# capsenbrd.net
KiCad netlist of a schematic drawn in EAGLE
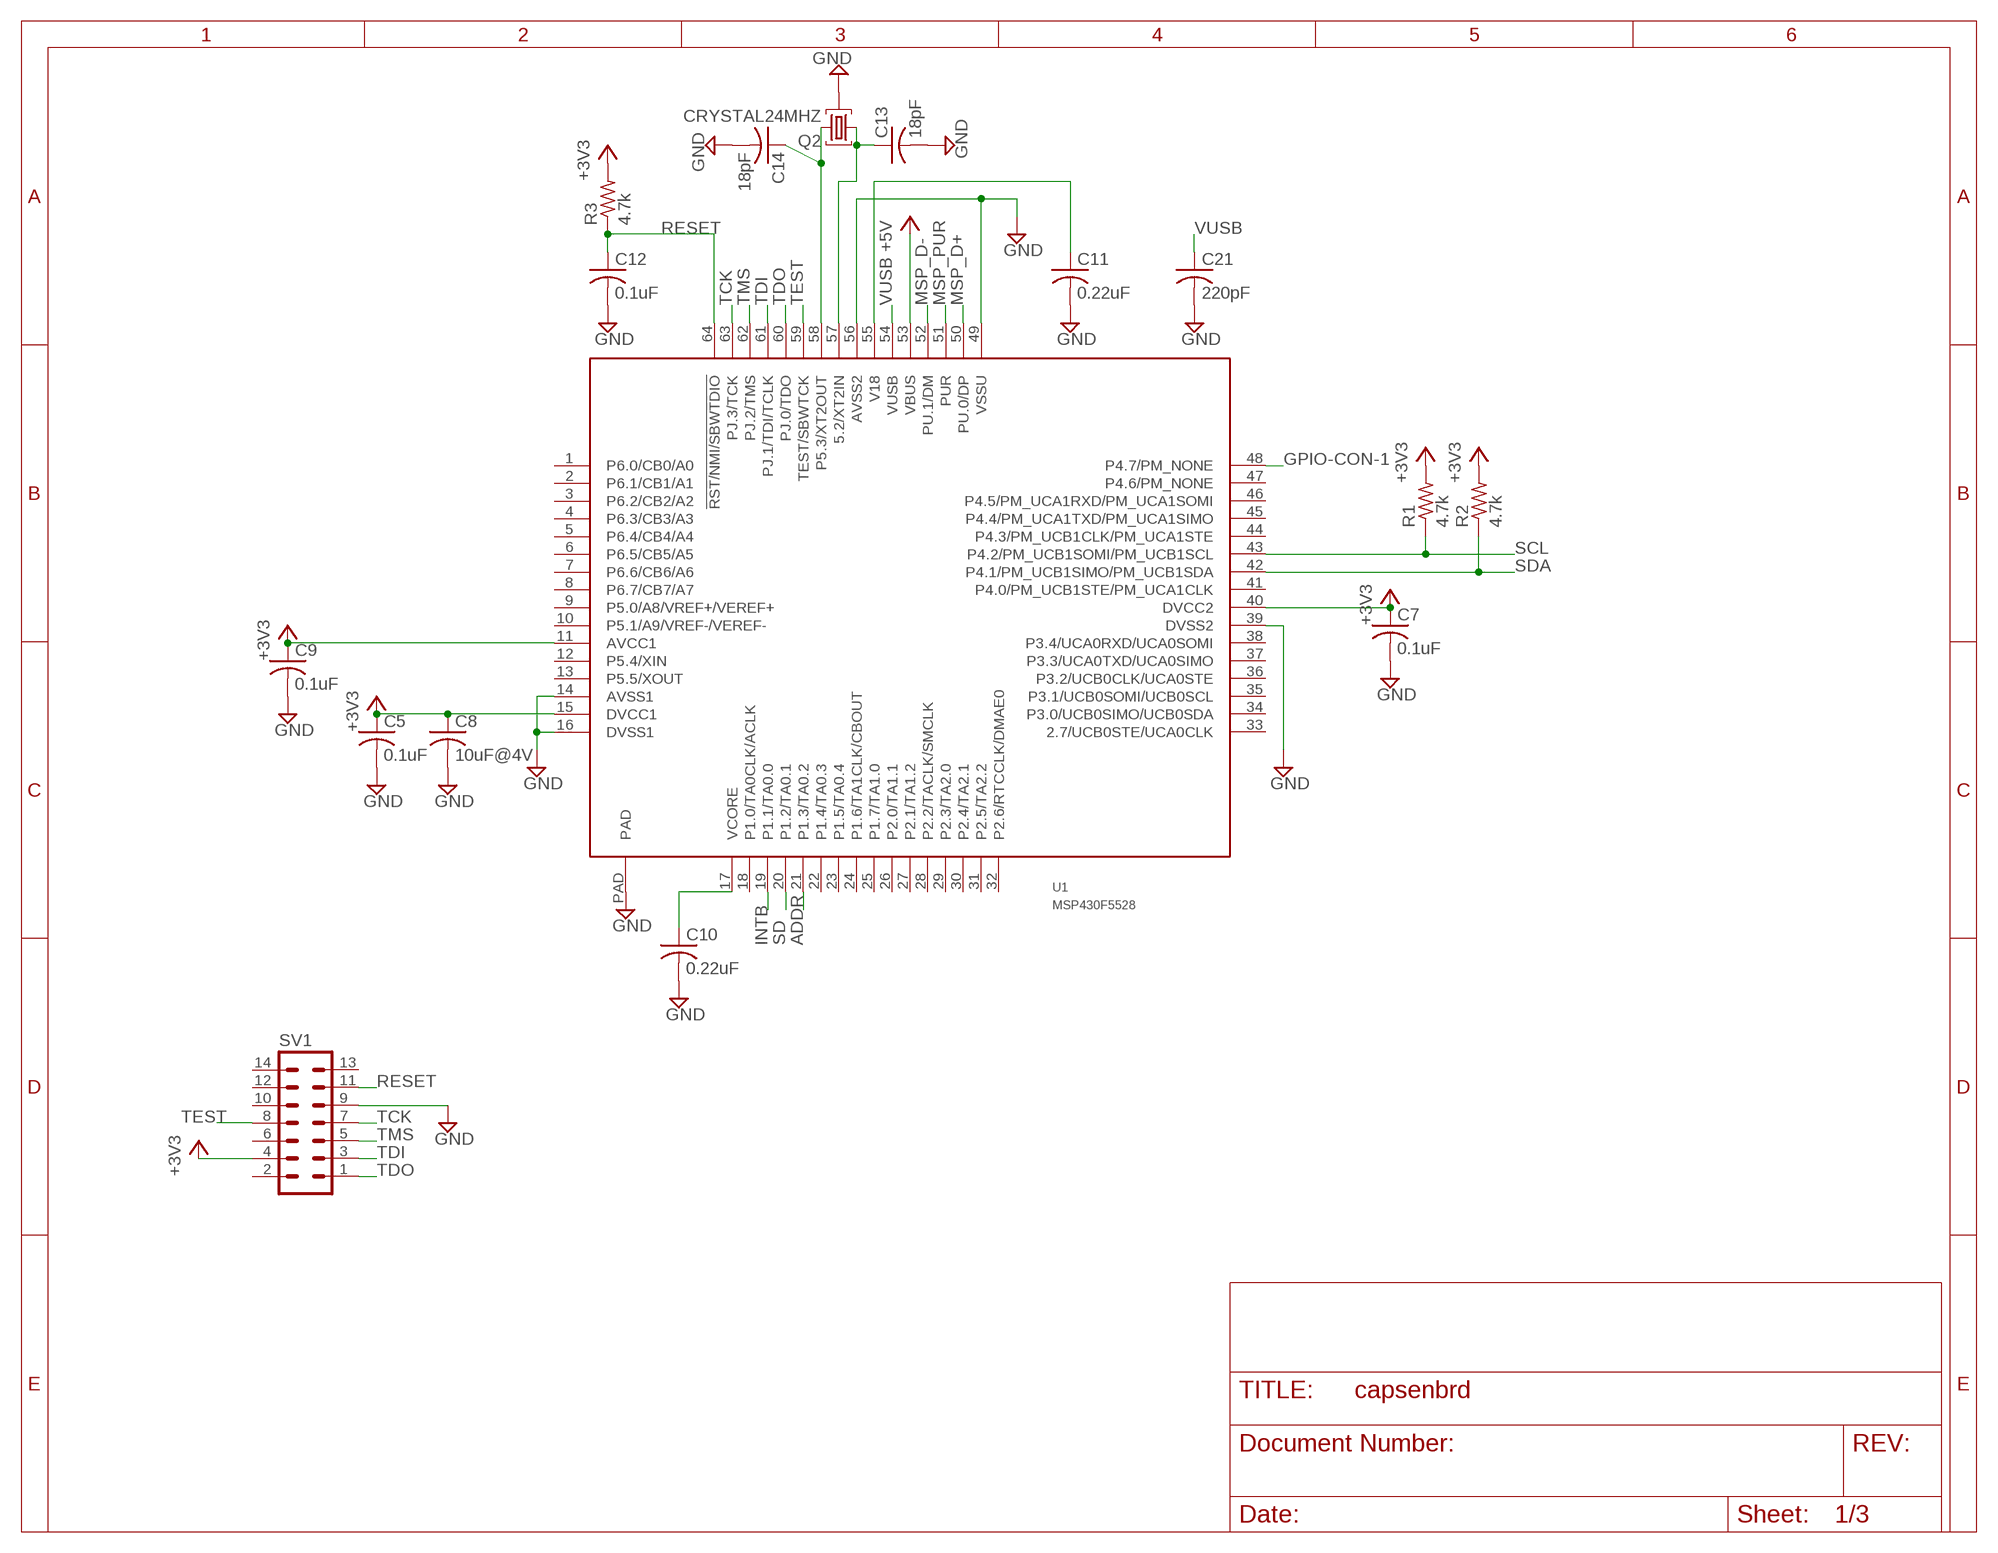
[diagram p0: schematic, sheet 1]
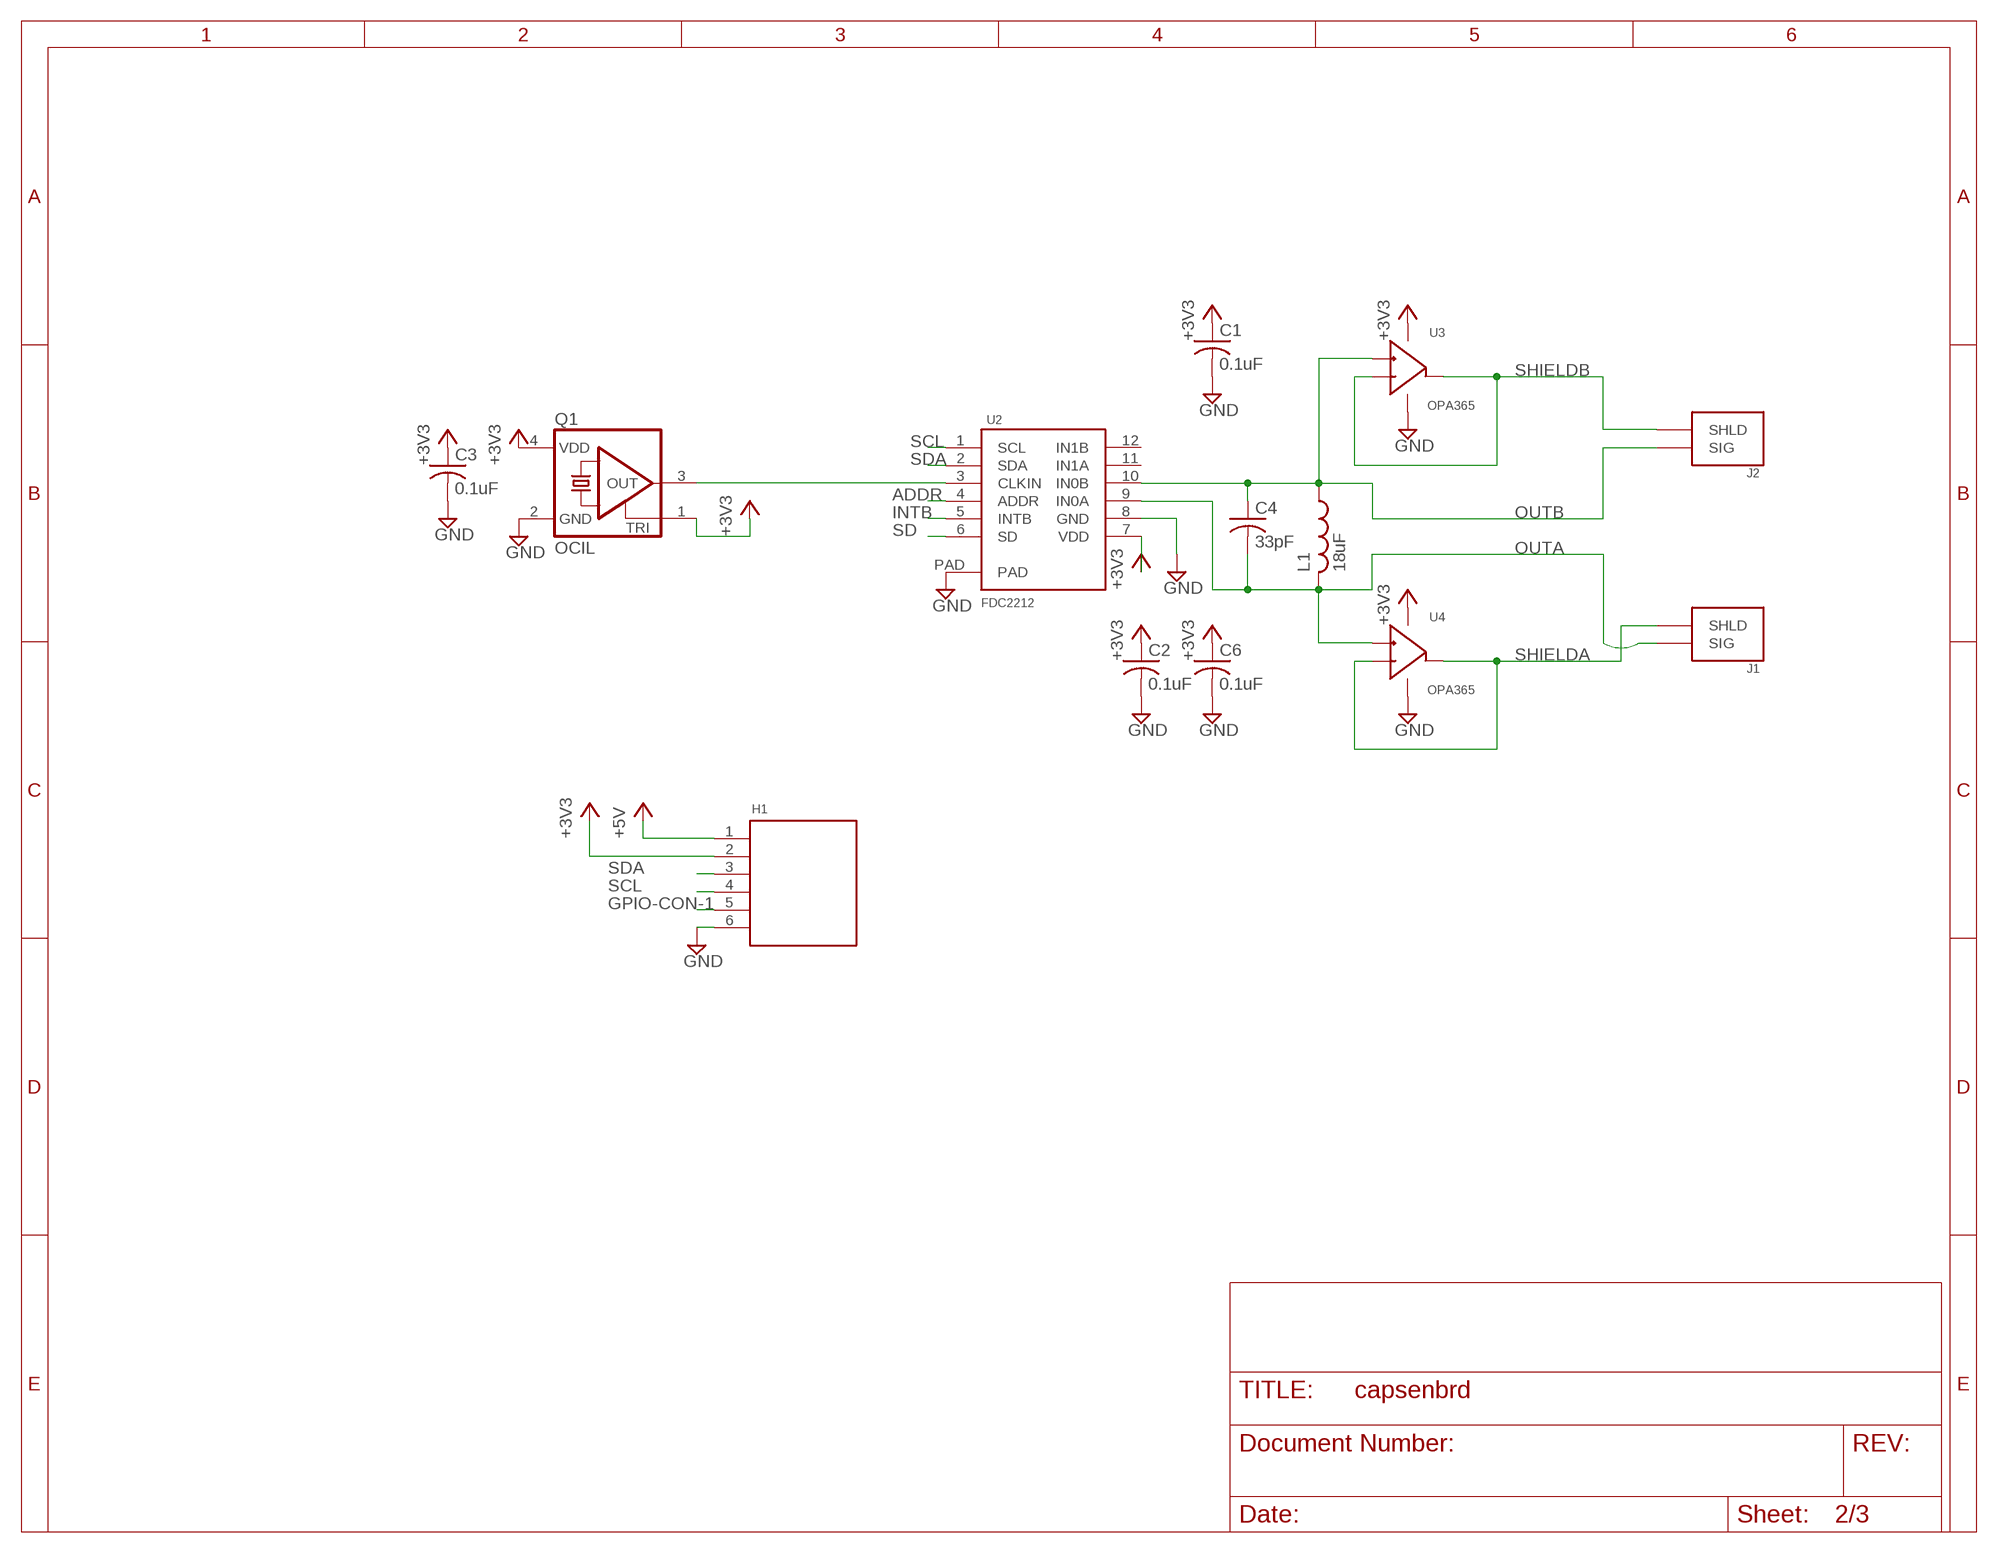
[diagram p1: schematic, sheet 2]
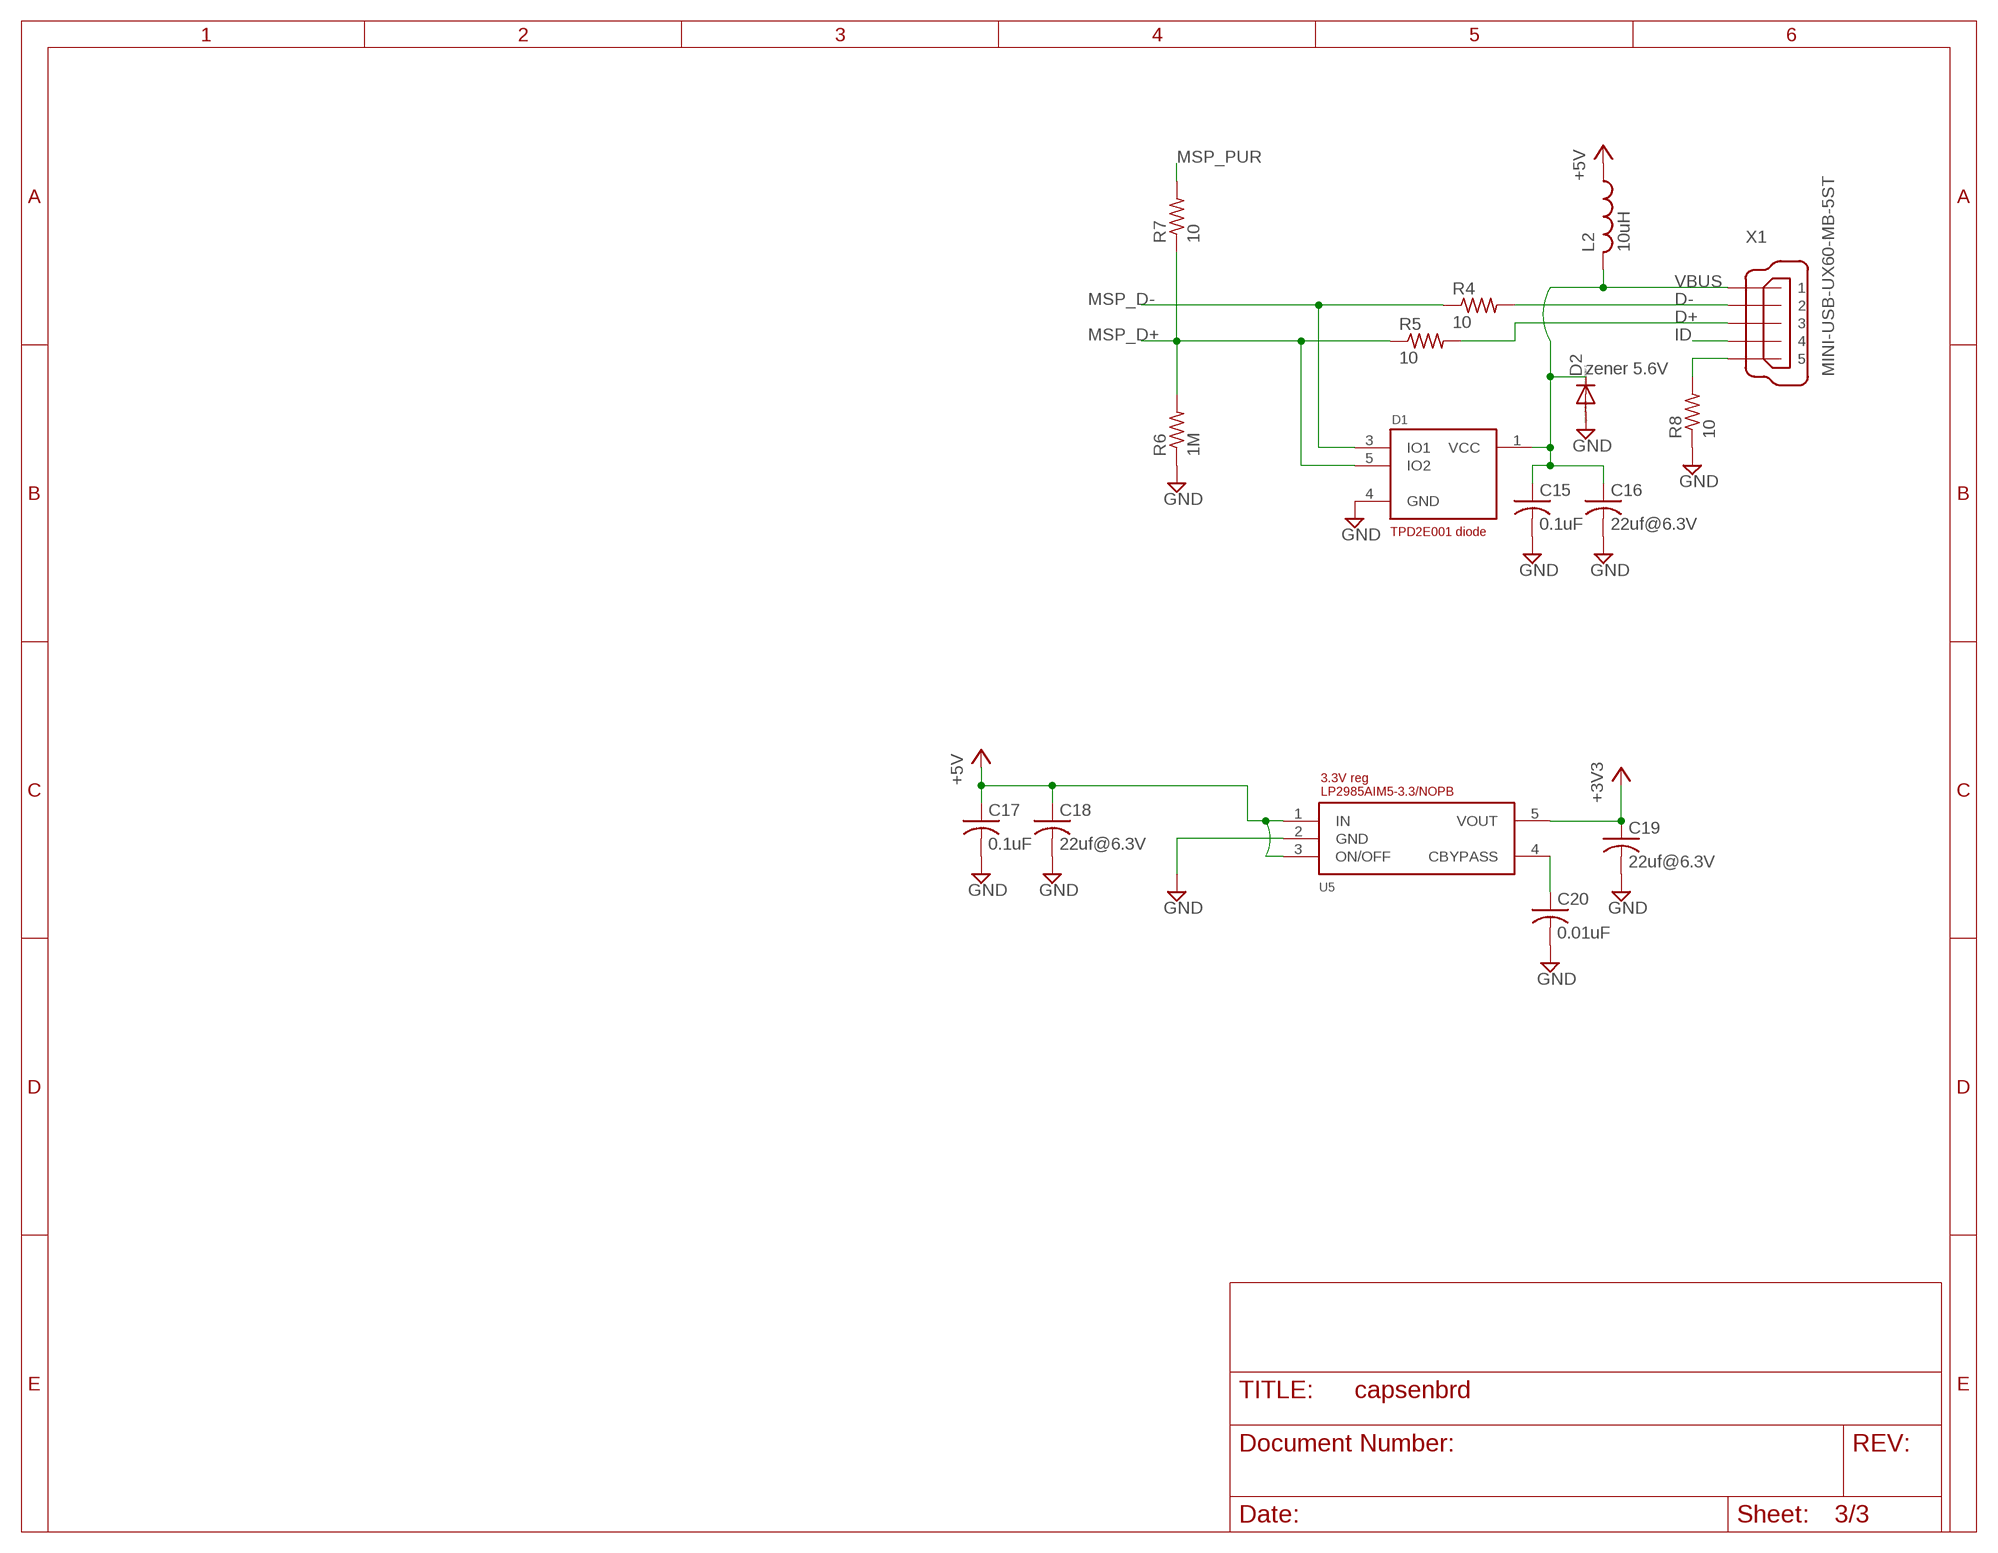
[diagram p2: schematic, sheet 3]

(export (version "E")
  (design (tool "Eeschema 10.0.6"))
  (components
    (comp (ref "C1")
      (value "0.1uF")
      (footprint "eagle-import:C0603")
      (fields (field (name "MFG") "yageo") (field (name "MPN") "CC0603KRX7R7BB104"))
      (libsource (lib "eagle-import") (part "C-USC06030.1UF"))
    )
    (comp (ref "C2")
      (value "0.1uF")
      (footprint "eagle-import:C0603")
      (fields (field (name "MFG") "yageo") (field (name "MPN") "CC0603KRX7R7BB104"))
      (libsource (lib "eagle-import") (part "C-USC06030.1UF"))
    )
    (comp (ref "C3")
      (value "0.1uF")
      (footprint "eagle-import:C0603")
      (fields (field (name "MFG") "yageo") (field (name "MPN") "CC0603KRX7R7BB104"))
      (libsource (lib "eagle-import") (part "C-USC06030.1UF"))
    )
    (comp (ref "C4")
      (value "33pF")
      (footprint "eagle-import:C0603")
      (fields (field (name "MFG") "murata") (field (name "MPN") "GRM1885C1H330JA01D"))
      (libsource (lib "eagle-import") (part "C-USC0603-33PF-"))
    )
    (comp (ref "C6")
      (value "0.1uF")
      (footprint "eagle-import:C0603")
      (fields (field (name "MFG") "yageo") (field (name "MPN") "CC0603KRX7R7BB104"))
      (libsource (lib "eagle-import") (part "C-USC06030.1UF"))
    )
    (comp (ref "H1")
      (value "CON-6-1")
      (footprint "eagle-import:10114828-10106LF")
      (fields (field (name "MFG") "FCI") (field (name "MPN") " 10114828-10106LF "))
      (libsource (lib "eagle-import") (part "CON-6-1"))
    )
    (comp (ref "J1")
      (value "SMA-SMT-")
      (footprint "eagle-import:0732511352")
      (fields (field (name "MFG") "molex") (field (name "MPN") "0732511352"))
      (libsource (lib "eagle-import") (part "SMA-SMT-"))
    )
    (comp (ref "J2")
      (value "SMA-SMT-")
      (footprint "eagle-import:0732511352")
      (fields (field (name "MFG") "molex") (field (name "MPN") "0732511352"))
      (libsource (lib "eagle-import") (part "SMA-SMT-"))
    )
    (comp (ref "L1")
      (value "18uF")
      (footprint "eagle-import:L1210")
      (fields (field (name "MFG") "bourns") (field (name "MPN") " CMH322522-180KL "))
      (libsource (lib "eagle-import") (part "L-USL1210-18UF-"))
    )
    (comp (ref "Q1")
      (value "OCIL")
      (footprint "eagle-import:625L3C040M00000")
      (fields (field (name "MFG") "CTS") (field (name "MPN") "625L3C040M00000"))
      (libsource (lib "eagle-import") (part "OCIL"))
    )
    (comp (ref "U2")
      (value "FDC2212")
      (footprint "eagle-import:-WSON")
      (fields (field (name "MFG") "TI"))
      (libsource (lib "eagle-import") (part "FDC2212"))
    )
    (comp (ref "U3")
      (value "OPA365")
      (footprint "eagle-import:-DBV")
      (fields (field (name "MFG") "TI") (field (name "MPN") "OPA365AIDBVR"))
      (libsource (lib "eagle-import") (part "OPA365"))
    )
    (comp (ref "U4")
      (value "OPA365")
      (footprint "eagle-import:-DBV")
      (fields (field (name "MFG") "TI") (field (name "MPN") "OPA365AIDBVR"))
      (libsource (lib "eagle-import") (part "OPA365"))
    )
    (comp (ref "C15")
      (value "0.1uF")
      (footprint "eagle-import:C0603")
      (fields (field (name "MFG") "yageo") (field (name "MPN") "CC0603KRX7R7BB104"))
      (libsource (lib "eagle-import") (part "C-USC06030.1UF"))
    )
    (comp (ref "C16")
      (value "22uf@6.3V")
      (footprint "eagle-import:C0603")
      (fields (field (name "MFG") "samsung") (field (name "MPN") "CL10A226MQ8NRNC"))
      (libsource (lib "eagle-import") (part "C-USC060322UF"))
    )
    (comp (ref "C17")
      (value "0.1uF")
      (footprint "eagle-import:C0603")
      (fields (field (name "MFG") "yageo") (field (name "MPN") "CC0603KRX7R7BB104"))
      (libsource (lib "eagle-import") (part "C-USC06030.1UF"))
    )
    (comp (ref "C18")
      (value "22uf@6.3V")
      (footprint "eagle-import:C0603")
      (fields (field (name "MFG") "samsung") (field (name "MPN") "CL10A226MQ8NRNC"))
      (libsource (lib "eagle-import") (part "C-USC060322UF"))
    )
    (comp (ref "C19")
      (value "22uf@6.3V")
      (footprint "eagle-import:C0603")
      (fields (field (name "MFG") "samsung") (field (name "MPN") "CL10A226MQ8NRNC"))
      (libsource (lib "eagle-import") (part "C-USC060322UF"))
    )
    (comp (ref "C20")
      (value "0.01uF")
      (footprint "eagle-import:C0603")
      (fields (field (name "MFG") "murata") (field (name "MPN") "GRM1885C1H103JA01D"))
      (libsource (lib "eagle-import") (part "C-USC0603-0.01UF-"))
    )
    (comp (ref "D1")
      (value "USB-DIODE")
      (footprint "eagle-import:-DRL")
      (fields (field (name "MFG") "ti") (field (name "MPN") "TPD2E001DRLRG4"))
      (libsource (lib "eagle-import") (part "USB-DIODE"))
    )
    (comp (ref "D2")
      (value "zener 5.6V")
      (footprint "eagle-import:SOD123")
      (fields (field (name "MFG") "diodes inc") (field (name "MPN") " MMSZ5232B-7-F"))
      (libsource (lib "eagle-import") (part "DIODE-SOD123"))
    )
    (comp (ref "L2")
      (value "10uH")
      (footprint "eagle-import:VLS201610ET")
      (fields (field (name "MFG") "tdk") (field (name "MPN") " VLS201610ET-100M "))
      (libsource (lib "eagle-import") (part "L-USVLS201610ET-10UH-"))
    )
    (comp (ref "R4")
      (value "10")
      (footprint "eagle-import:R0603")
      (fields (field (name "MFG") "panasonic") (field (name "MPN") "ERJ-3EKF10R0V "))
      (libsource (lib "eagle-import") (part "R-US_R060310"))
    )
    (comp (ref "R5")
      (value "10")
      (footprint "eagle-import:R0603")
      (fields (field (name "MFG") "panasonic") (field (name "MPN") "ERJ-3EKF10R0V "))
      (libsource (lib "eagle-import") (part "R-US_R060310"))
    )
    (comp (ref "R6")
      (value "1M")
      (footprint "eagle-import:R0603")
      (fields (field (name "MFG") "panasonic") (field (name "MPN") " ERJ-3EKF1004V "))
      (libsource (lib "eagle-import") (part "R-US_R06031M"))
    )
    (comp (ref "R7")
      (value "10")
      (footprint "eagle-import:R0603")
      (fields (field (name "MFG") "panasonic") (field (name "MPN") "ERJ-3EKF10R0V "))
      (libsource (lib "eagle-import") (part "R-US_R060310"))
    )
    (comp (ref "R8")
      (value "10")
      (footprint "eagle-import:R0603")
      (fields (field (name "MFG") "panasonic") (field (name "MPN") "ERJ-3EKF10R0V "))
      (libsource (lib "eagle-import") (part "R-US_R060310"))
    )
    (comp (ref "U5")
      (value "3.3V")
      (footprint "eagle-import:-DBV")
      (fields (field (name "MFG") "TI") (field (name "MPN") "LP2985AIM5-3.3/NOPB"))
      (libsource (lib "eagle-import") (part "VREG3.3V3.3V"))
    )
    (comp (ref "X1")
      (value "MINI-USB-UX60-MB-5ST")
      (footprint "eagle-import:UX60-MB-5ST")
      (fields (field (name "MFG") "Hirose") (field (name "MPN") "UX60-MB-5ST "))
      (libsource (lib "eagle-import") (part "MINI-USB-UX60-MB-5ST"))
    )
    (comp (ref "C5")
      (value "0.1uF")
      (footprint "eagle-import:C0603")
      (fields (field (name "MFG") "yageo") (field (name "MPN") "CC0603KRX7R7BB104"))
      (libsource (lib "eagle-import") (part "C-USC06030.1UF"))
    )
    (comp (ref "C7")
      (value "0.1uF")
      (footprint "eagle-import:C0603")
      (fields (field (name "MFG") "yageo") (field (name "MPN") "CC0603KRX7R7BB104"))
      (libsource (lib "eagle-import") (part "C-USC06030.1UF"))
    )
    (comp (ref "C8")
      (value "10uF@4V")
      (footprint "eagle-import:C0603")
      (fields (field (name "MFG") "murata") (field (name "MPN") "GRM188R60G106ME47D"))
      (libsource (lib "eagle-import") (part "C-USC060310UF"))
    )
    (comp (ref "C9")
      (value "0.1uF")
      (footprint "eagle-import:C0603")
      (fields (field (name "MFG") "yageo") (field (name "MPN") "CC0603KRX7R7BB104"))
      (libsource (lib "eagle-import") (part "C-USC06030.1UF"))
    )
    (comp (ref "C10")
      (value "0.22uF")
      (footprint "eagle-import:C0603")
      (fields (field (name "MFG") "samsung") (field (name "MPN") "CL10B224KO8NNNC"))
      (libsource (lib "eagle-import") (part "C-USC06030.22UF"))
    )
    (comp (ref "C11")
      (value "0.22uF")
      (footprint "eagle-import:C0603")
      (fields (field (name "MFG") "samsung") (field (name "MPN") "CL10B224KO8NNNC"))
      (libsource (lib "eagle-import") (part "C-USC06030.22UF"))
    )
    (comp (ref "C12")
      (value "0.1uF")
      (footprint "eagle-import:C0603")
      (fields (field (name "MFG") "yageo") (field (name "MPN") "CC0603KRX7R7BB104"))
      (libsource (lib "eagle-import") (part "C-USC06030.1UF"))
    )
    (comp (ref "C13")
      (value "18pF")
      (footprint "eagle-import:C0603")
      (fields (field (name "MFG") "panasonic") (field (name "MPN") "CL10C180JB8NNNC"))
      (libsource (lib "eagle-import") (part "C-USC060318PF"))
    )
    (comp (ref "C14")
      (value "18pF")
      (footprint "eagle-import:C0603")
      (fields (field (name "MFG") "panasonic") (field (name "MPN") "CL10C180JB8NNNC"))
      (libsource (lib "eagle-import") (part "C-USC060318PF"))
    )
    (comp (ref "C21")
      (value "220pF")
      (footprint "eagle-import:C0603")
      (fields (field (name "MFG") "murata") (field (name "MPN") "GRM1885C1H221JA01D"))
      (libsource (lib "eagle-import") (part "C-USC0603-220PF-"))
    )
    (comp (ref "Q2")
      (value "CRYSTAL24MHZ")
      (footprint "eagle-import:ABM8")
      (fields (field (name "MFG") "Abracon") (field (name "MPN") "ABM8-24.000MHZ-B2-T "))
      (libsource (lib "eagle-import") (part "CRYSTAL24MHZ"))
    )
    (comp (ref "R1")
      (value "4.7k")
      (footprint "eagle-import:R0603")
      (fields (field (name "MFG") "panasonic") (field (name "MPN") " ERJ-3GEYJ472V "))
      (libsource (lib "eagle-import") (part "R-US_R06034.7K"))
    )
    (comp (ref "R2")
      (value "4.7k")
      (footprint "eagle-import:R0603")
      (fields (field (name "MFG") "panasonic") (field (name "MPN") " ERJ-3GEYJ472V "))
      (libsource (lib "eagle-import") (part "R-US_R06034.7K"))
    )
    (comp (ref "R3")
      (value "4.7k")
      (footprint "eagle-import:R0603")
      (fields (field (name "MFG") "panasonic") (field (name "MPN") " ERJ-3GEYJ472V "))
      (libsource (lib "eagle-import") (part "R-US_R06034.7K"))
    )
    (comp (ref "SV1")
      (value "MA07-2SMT")
      (footprint "eagle-import:MA07-2-SMT")
      (libsource (lib "eagle-import") (part "MA07-2SMT"))
    )
    (comp (ref "U1")
      (value "MSP430F5528")
      (footprint "eagle-import:-RGC-N64")
      (fields (field (name "MFG") "TI") (field (name "MPN") "MSP430F5528IRGCR"))
      (libsource (lib "eagle-import") (part "MSP430F5528"))
    )
  )
  (nets
    (net (code "1") (name "+3V3") (class "Default")
      (node (ref "C1") (pin "1") (pinfunction "1_1") (pintype "passive"))
      (node (ref "C19") (pin "1") (pinfunction "1_1") (pintype "passive"))
      (node (ref "C2") (pin "1") (pinfunction "1_1") (pintype "passive"))
      (node (ref "C3") (pin "1") (pinfunction "1_1") (pintype "passive"))
      (node (ref "C5") (pin "1") (pinfunction "1_1") (pintype "passive"))
      (node (ref "C6") (pin "1") (pinfunction "1_1") (pintype "passive"))
      (node (ref "C7") (pin "1") (pinfunction "1_1") (pintype "passive"))
      (node (ref "C8") (pin "1") (pinfunction "1_1") (pintype "passive"))
      (node (ref "C9") (pin "1") (pinfunction "1_1") (pintype "passive"))
      (node (ref "H1") (pin "2") (pinfunction "P$2_2") (pintype "bidirectional"))
      (node (ref "Q1") (pin "1") (pinfunction "TRI_1") (pintype "input"))
      (node (ref "Q1") (pin "4") (pinfunction "VDD_4") (pintype "power_in"))
      (node (ref "R1") (pin "2") (pinfunction "2_2") (pintype "passive"))
      (node (ref "R2") (pin "2") (pinfunction "2_2") (pintype "passive"))
      (node (ref "R3") (pin "2") (pinfunction "2_2") (pintype "passive"))
      (node (ref "SV1") (pin "4") (pinfunction "4_4") (pintype "passive"))
      (node (ref "U1") (pin "11") (pinfunction "AVCC1_11") (pintype "bidirectional"))
      (node (ref "U1") (pin "15") (pinfunction "DVCC1_15") (pintype "bidirectional"))
      (node (ref "U1") (pin "40") (pinfunction "DVCC2_40") (pintype "bidirectional"))
      (node (ref "U2") (pin "7") (pinfunction "VDD_7") (pintype "bidirectional"))
      (node (ref "U3") (pin "5") (pinfunction "V+_5") (pintype "bidirectional"))
      (node (ref "U4") (pin "5") (pinfunction "V+_5") (pintype "bidirectional"))
      (node (ref "U5") (pin "5") (pinfunction "VOUT_5") (pintype "bidirectional"))
    )
    (net (code "2") (name "+5V") (class "Default")
      (node (ref "C17") (pin "1") (pinfunction "1_1") (pintype "passive"))
      (node (ref "C18") (pin "1") (pinfunction "1_1") (pintype "passive"))
      (node (ref "H1") (pin "1") (pinfunction "P$1_1") (pintype "bidirectional"))
      (node (ref "L2") (pin "P$1") (pinfunction "1_P$1") (pintype "passive"))
      (node (ref "U1") (pin "53") (pinfunction "VBUS_53") (pintype "bidirectional"))
      (node (ref "U5") (pin "1") (pinfunction "IN_1") (pintype "bidirectional"))
      (node (ref "U5") (pin "3") (pinfunction "ON/OFF_3") (pintype "bidirectional"))
    )
    (net (code "3") (name "ADDR") (class "Default")
      (node (ref "U1") (pin "21") (pinfunction "P1.3/TA0.2_21") (pintype "bidirectional"))
      (node (ref "U2") (pin "4") (pinfunction "ADDR_4") (pintype "bidirectional"))
    )
    (net (code "4") (name "D+") (class "Default")
      (node (ref "R5") (pin "2") (pinfunction "2_2") (pintype "passive"))
      (node (ref "X1") (pin "3") (pinfunction "3_3") (pintype "input"))
    )
    (net (code "5") (name "D-") (class "Default")
      (node (ref "R4") (pin "2") (pinfunction "2_2") (pintype "passive"))
      (node (ref "X1") (pin "2") (pinfunction "2_2") (pintype "input"))
    )
    (net (code "6") (name "GND") (class "Default")
      (node (ref "C1") (pin "2") (pinfunction "2_2") (pintype "passive"))
      (node (ref "C10") (pin "2") (pinfunction "2_2") (pintype "passive"))
      (node (ref "C11") (pin "2") (pinfunction "2_2") (pintype "passive"))
      (node (ref "C12") (pin "2") (pinfunction "2_2") (pintype "passive"))
      (node (ref "C13") (pin "2") (pinfunction "2_2") (pintype "passive"))
      (node (ref "C14") (pin "2") (pinfunction "2_2") (pintype "passive"))
      (node (ref "C15") (pin "2") (pinfunction "2_2") (pintype "passive"))
      (node (ref "C16") (pin "2") (pinfunction "2_2") (pintype "passive"))
      (node (ref "C17") (pin "2") (pinfunction "2_2") (pintype "passive"))
      (node (ref "C18") (pin "2") (pinfunction "2_2") (pintype "passive"))
      (node (ref "C19") (pin "2") (pinfunction "2_2") (pintype "passive"))
      (node (ref "C2") (pin "2") (pinfunction "2_2") (pintype "passive"))
      (node (ref "C20") (pin "2") (pinfunction "2_2") (pintype "passive"))
      (node (ref "C21") (pin "2") (pinfunction "2_2") (pintype "passive"))
      (node (ref "C3") (pin "2") (pinfunction "2_2") (pintype "passive"))
      (node (ref "C5") (pin "2") (pinfunction "2_2") (pintype "passive"))
      (node (ref "C6") (pin "2") (pinfunction "2_2") (pintype "passive"))
      (node (ref "C7") (pin "2") (pinfunction "2_2") (pintype "passive"))
      (node (ref "C8") (pin "2") (pinfunction "2_2") (pintype "passive"))
      (node (ref "C9") (pin "2") (pinfunction "2_2") (pintype "passive"))
      (node (ref "D1") (pin "4") (pinfunction "GND_4") (pintype "bidirectional"))
      (node (ref "D2") (pin "A") (pinfunction "A_A") (pintype "passive"))
      (node (ref "H1") (pin "6") (pinfunction "P$6_6") (pintype "bidirectional"))
      (node (ref "Q1") (pin "2") (pinfunction "GND_2") (pintype "power_in"))
      (node (ref "Q2") (pin "2") (pinfunction "2_2") (pintype "passive"))
      (node (ref "Q2") (pin "4") (pinfunction "2_4") (pintype "passive"))
      (node (ref "R6") (pin "1") (pinfunction "1_1") (pintype "passive"))
      (node (ref "R8") (pin "1") (pinfunction "1_1") (pintype "passive"))
      (node (ref "SV1") (pin "9") (pinfunction "9_9") (pintype "passive"))
      (node (ref "U1") (pin "14") (pinfunction "AVSS1_14") (pintype "bidirectional"))
      (node (ref "U1") (pin "16") (pinfunction "DVSS1_16") (pintype "bidirectional"))
      (node (ref "U1") (pin "39") (pinfunction "DVSS2_39") (pintype "bidirectional"))
      (node (ref "U1") (pin "49") (pinfunction "VSSU_49") (pintype "bidirectional"))
      (node (ref "U1") (pin "56") (pinfunction "AVSS2_56") (pintype "bidirectional"))
      (node (ref "U1") (pin "PAD") (pinfunction "PAD_PAD") (pintype "bidirectional"))
      (node (ref "U2") (pin "8") (pinfunction "GND_8") (pintype "bidirectional"))
      (node (ref "U2") (pin "PAD") (pinfunction "PAD_PAD") (pintype "bidirectional"))
      (node (ref "U3") (pin "2") (pinfunction "V-_2") (pintype "bidirectional"))
      (node (ref "U4") (pin "2") (pinfunction "V-_2") (pintype "bidirectional"))
      (node (ref "U5") (pin "2") (pinfunction "GND_2") (pintype "bidirectional"))
    )
    (net (code "7") (name "GPIO-CON-1") (class "Default")
      (node (ref "H1") (pin "5") (pinfunction "P$5_5") (pintype "bidirectional"))
      (node (ref "U1") (pin "48") (pinfunction "P4.7/PM_NONE_48") (pintype "bidirectional"))
    )
    (net (code "8") (name "ID") (class "Default")
      (node (ref "X1") (pin "4") (pinfunction "4_4") (pintype "input"))
    )
    (net (code "9") (name "INTB") (class "Default")
      (node (ref "U1") (pin "19") (pinfunction "P1.1/TA0.0_19") (pintype "bidirectional"))
      (node (ref "U2") (pin "5") (pinfunction "INTB_5") (pintype "bidirectional"))
    )
    (net (code "10") (name "MSP_D+") (class "Default")
      (node (ref "D1") (pin "5") (pinfunction "IO2_5") (pintype "bidirectional"))
      (node (ref "R5") (pin "1") (pinfunction "1_1") (pintype "passive"))
      (node (ref "R6") (pin "2") (pinfunction "2_2") (pintype "passive"))
      (node (ref "R7") (pin "1") (pinfunction "1_1") (pintype "passive"))
      (node (ref "U1") (pin "50") (pinfunction "PU.0/DP_50") (pintype "bidirectional"))
    )
    (net (code "11") (name "MSP_D-") (class "Default")
      (node (ref "D1") (pin "3") (pinfunction "IO1_3") (pintype "bidirectional"))
      (node (ref "R4") (pin "1") (pinfunction "1_1") (pintype "passive"))
      (node (ref "U1") (pin "52") (pinfunction "PU.1/DM_52") (pintype "bidirectional"))
    )
    (net (code "12") (name "MSP_PUR") (class "Default")
      (node (ref "R7") (pin "2") (pinfunction "2_2") (pintype "passive"))
      (node (ref "U1") (pin "51") (pinfunction "PUR_51") (pintype "bidirectional"))
    )
    (net (code "13") (name "Net-(Q1-OUT)") (class "Default")
      (node (ref "Q1") (pin "3") (pinfunction "OUT_3") (pintype "output"))
      (node (ref "U2") (pin "3") (pinfunction "CLKIN_3") (pintype "bidirectional"))
    )
    (net (code "14") (name "Net-(R8-Pad2)") (class "Default")
      (node (ref "R8") (pin "2") (pinfunction "2_2") (pintype "passive"))
      (node (ref "X1") (pin "5") (pinfunction "5_5") (pintype "input"))
    )
    (net (code "15") (name "Net-(U1-5.2{slash}XT2IN)") (class "Default")
      (node (ref "C13") (pin "1") (pinfunction "1_1") (pintype "passive"))
      (node (ref "Q2") (pin "1") (pinfunction "1_1") (pintype "passive"))
      (node (ref "U1") (pin "57") (pinfunction "5.2/XT2IN_57") (pintype "bidirectional"))
    )
    (net (code "16") (name "Net-(U1-P5.3{slash}XT2OUT)") (class "Default")
      (node (ref "C14") (pin "1") (pinfunction "1_1") (pintype "passive"))
      (node (ref "Q2") (pin "3") (pinfunction "3_3") (pintype "passive"))
      (node (ref "U1") (pin "58") (pinfunction "P5.3/XT2OUT_58") (pintype "bidirectional"))
    )
    (net (code "17") (name "Net-(U1-V18)") (class "Default")
      (node (ref "C11") (pin "1") (pinfunction "1_1") (pintype "passive"))
      (node (ref "U1") (pin "55") (pinfunction "V18_55") (pintype "bidirectional"))
    )
    (net (code "18") (name "Net-(U1-VCORE)") (class "Default")
      (node (ref "C10") (pin "1") (pinfunction "1_1") (pintype "passive"))
      (node (ref "U1") (pin "17") (pinfunction "VCORE_17") (pintype "bidirectional"))
    )
    (net (code "19") (name "Net-(U5-CBYPASS)") (class "Default")
      (node (ref "C20") (pin "1") (pinfunction "1_1") (pintype "passive"))
      (node (ref "U5") (pin "4") (pinfunction "CBYPASS_4") (pintype "bidirectional"))
    )
    (net (code "20") (name "OUTA") (class "Default")
      (node (ref "C4") (pin "2") (pinfunction "2_2") (pintype "passive"))
      (node (ref "J1") (pin "SIG") (pinfunction "SIG_SIG") (pintype "bidirectional"))
      (node (ref "L1") (pin "P$2") (pinfunction "2_P$2") (pintype "passive"))
      (node (ref "U2") (pin "9") (pinfunction "IN0A_9") (pintype "bidirectional"))
      (node (ref "U4") (pin "3") (pinfunction "IN+_3") (pintype "bidirectional"))
    )
    (net (code "21") (name "OUTB") (class "Default")
      (node (ref "C4") (pin "1") (pinfunction "1_1") (pintype "passive"))
      (node (ref "J2") (pin "SIG") (pinfunction "SIG_SIG") (pintype "bidirectional"))
      (node (ref "L1") (pin "P$1") (pinfunction "1_P$1") (pintype "passive"))
      (node (ref "U2") (pin "10") (pinfunction "IN0B_10") (pintype "bidirectional"))
      (node (ref "U3") (pin "3") (pinfunction "IN+_3") (pintype "bidirectional"))
    )
    (net (code "22") (name "RESET") (class "Default")
      (node (ref "C12") (pin "1") (pinfunction "1_1") (pintype "passive"))
      (node (ref "R3") (pin "1") (pinfunction "1_1") (pintype "passive"))
      (node (ref "SV1") (pin "11") (pinfunction "11_11") (pintype "passive"))
      (node (ref "U1") (pin "64") (pinfunction "~{RST/NMI/SBWTDIO}_64") (pintype "bidirectional"))
    )
    (net (code "23") (name "SCL") (class "Default")
      (node (ref "H1") (pin "4") (pinfunction "P$4_4") (pintype "bidirectional"))
      (node (ref "R1") (pin "1") (pinfunction "1_1") (pintype "passive"))
      (node (ref "U1") (pin "43") (pinfunction "P4.2/PM_UCB1SOMI/PM_UCB1SCL_43") (pintype "bidirectional"))
      (node (ref "U2") (pin "1") (pinfunction "SCL_1") (pintype "bidirectional"))
    )
    (net (code "24") (name "SD") (class "Default")
      (node (ref "U1") (pin "20") (pinfunction "P1.2/TA0.1_20") (pintype "bidirectional"))
      (node (ref "U2") (pin "6") (pinfunction "SD_6") (pintype "bidirectional"))
    )
    (net (code "25") (name "SDA") (class "Default")
      (node (ref "H1") (pin "3") (pinfunction "P$3_3") (pintype "bidirectional"))
      (node (ref "R2") (pin "1") (pinfunction "1_1") (pintype "passive"))
      (node (ref "U1") (pin "42") (pinfunction "P4.1/PM_UCB1SIMO/PM_UCB1SDA_42") (pintype "bidirectional"))
      (node (ref "U2") (pin "2") (pinfunction "SDA_2") (pintype "bidirectional"))
    )
    (net (code "26") (name "SHIELDA") (class "Default")
      (node (ref "J1") (pin "SHLD1") (pinfunction "SHLD_SHLD1") (pintype "bidirectional"))
      (node (ref "J1") (pin "SHLD2") (pinfunction "SHLD_SHLD2") (pintype "bidirectional"))
      (node (ref "J1") (pin "SHLD3") (pinfunction "SHLD_SHLD3") (pintype "bidirectional"))
      (node (ref "J1") (pin "SHLD4") (pinfunction "SHLD_SHLD4") (pintype "bidirectional"))
      (node (ref "U4") (pin "1") (pinfunction "VOUT_1") (pintype "bidirectional"))
      (node (ref "U4") (pin "4") (pinfunction "IN-_4") (pintype "bidirectional"))
    )
    (net (code "27") (name "SHIELDB") (class "Default")
      (node (ref "J2") (pin "SHLD1") (pinfunction "SHLD_SHLD1") (pintype "bidirectional"))
      (node (ref "J2") (pin "SHLD2") (pinfunction "SHLD_SHLD2") (pintype "bidirectional"))
      (node (ref "J2") (pin "SHLD3") (pinfunction "SHLD_SHLD3") (pintype "bidirectional"))
      (node (ref "J2") (pin "SHLD4") (pinfunction "SHLD_SHLD4") (pintype "bidirectional"))
      (node (ref "U3") (pin "1") (pinfunction "VOUT_1") (pintype "bidirectional"))
      (node (ref "U3") (pin "4") (pinfunction "IN-_4") (pintype "bidirectional"))
    )
    (net (code "28") (name "TCK") (class "Default")
      (node (ref "SV1") (pin "7") (pinfunction "7_7") (pintype "passive"))
      (node (ref "U1") (pin "63") (pinfunction "PJ.3/TCK_63") (pintype "bidirectional"))
    )
    (net (code "29") (name "TDI") (class "Default")
      (node (ref "SV1") (pin "3") (pinfunction "3_3") (pintype "passive"))
      (node (ref "U1") (pin "61") (pinfunction "PJ.1/TDI/TCLK_61") (pintype "bidirectional"))
    )
    (net (code "30") (name "TDO") (class "Default")
      (node (ref "SV1") (pin "1") (pinfunction "1_1") (pintype "passive"))
      (node (ref "U1") (pin "60") (pinfunction "PJ.0/TDO_60") (pintype "bidirectional"))
    )
    (net (code "31") (name "TEST") (class "Default")
      (node (ref "SV1") (pin "8") (pinfunction "8_8") (pintype "passive"))
      (node (ref "U1") (pin "59") (pinfunction "TEST/SBWTCK_59") (pintype "bidirectional"))
    )
    (net (code "32") (name "TMS") (class "Default")
      (node (ref "SV1") (pin "5") (pinfunction "5_5") (pintype "passive"))
      (node (ref "U1") (pin "62") (pinfunction "PJ.2/TMS_62") (pintype "bidirectional"))
    )
    (net (code "33") (name "VBUS") (class "Default")
      (node (ref "C15") (pin "1") (pinfunction "1_1") (pintype "passive"))
      (node (ref "C16") (pin "1") (pinfunction "1_1") (pintype "passive"))
      (node (ref "D1") (pin "1") (pinfunction "VCC_1") (pintype "bidirectional"))
      (node (ref "D2") (pin "C") (pinfunction "C_C") (pintype "passive"))
      (node (ref "L2") (pin "P$2") (pinfunction "2_P$2") (pintype "passive"))
      (node (ref "X1") (pin "1") (pinfunction "1_1") (pintype "input"))
    )
    (net (code "34") (name "VUSB") (class "Default")
      (node (ref "C21") (pin "1") (pinfunction "1_1") (pintype "passive"))
      (node (ref "U1") (pin "54") (pinfunction "VUSB_54") (pintype "bidirectional"))
    )
    (net (code "35") (name "unconnected-(SV1-Pad2)") (class "Default")
      (node (ref "SV1") (pin "2") (pinfunction "2_2") (pintype "passive"))
    )
    (net (code "36") (name "unconnected-(SV1-Pad6)") (class "Default")
      (node (ref "SV1") (pin "6") (pinfunction "6_6") (pintype "passive"))
    )
    (net (code "37") (name "unconnected-(SV1-Pad10)") (class "Default")
      (node (ref "SV1") (pin "10") (pinfunction "10_10") (pintype "passive"))
    )
    (net (code "38") (name "unconnected-(SV1-Pad12)") (class "Default")
      (node (ref "SV1") (pin "12") (pinfunction "12_12") (pintype "passive"))
    )
    (net (code "39") (name "unconnected-(SV1-Pad13)") (class "Default")
      (node (ref "SV1") (pin "13") (pinfunction "13_13") (pintype "passive"))
    )
    (net (code "40") (name "unconnected-(SV1-Pad14)") (class "Default")
      (node (ref "SV1") (pin "14") (pinfunction "14_14") (pintype "passive"))
    )
    (net (code "41") (name "unconnected-(U1-2.7{slash}UCB0STE{slash}UCA0CLK-Pad33)") (class "Default")
      (node (ref "U1") (pin "33") (pinfunction "2.7/UCB0STE/UCA0CLK_33") (pintype "bidirectional"))
    )
    (net (code "42") (name "unconnected-(U1-P1.0{slash}TA0CLK{slash}ACLK-Pad18)") (class "Default")
      (node (ref "U1") (pin "18") (pinfunction "P1.0/TA0CLK/ACLK_18") (pintype "bidirectional"))
    )
    (net (code "43") (name "unconnected-(U1-P1.4{slash}TA0.3-Pad22)") (class "Default")
      (node (ref "U1") (pin "22") (pinfunction "P1.4/TA0.3_22") (pintype "bidirectional"))
    )
    (net (code "44") (name "unconnected-(U1-P1.5{slash}TA0.4-Pad23)") (class "Default")
      (node (ref "U1") (pin "23") (pinfunction "P1.5/TA0.4_23") (pintype "bidirectional"))
    )
    (net (code "45") (name "unconnected-(U1-P1.6{slash}TA1CLK{slash}CBOUT-Pad24)") (class "Default")
      (node (ref "U1") (pin "24") (pinfunction "P1.6/TA1CLK/CBOUT_24") (pintype "bidirectional"))
    )
    (net (code "46") (name "unconnected-(U1-P1.7{slash}TA1.0-Pad25)") (class "Default")
      (node (ref "U1") (pin "25") (pinfunction "P1.7/TA1.0_25") (pintype "bidirectional"))
    )
    (net (code "47") (name "unconnected-(U1-P2.0{slash}TA1.1-Pad26)") (class "Default")
      (node (ref "U1") (pin "26") (pinfunction "P2.0/TA1.1_26") (pintype "bidirectional"))
    )
    (net (code "48") (name "unconnected-(U1-P2.1{slash}TA1.2-Pad27)") (class "Default")
      (node (ref "U1") (pin "27") (pinfunction "P2.1/TA1.2_27") (pintype "bidirectional"))
    )
    (net (code "49") (name "unconnected-(U1-P2.2{slash}TACLK{slash}SMCLK-Pad28)") (class "Default")
      (node (ref "U1") (pin "28") (pinfunction "P2.2/TACLK/SMCLK_28") (pintype "bidirectional"))
    )
    (net (code "50") (name "unconnected-(U1-P2.3{slash}TA2.0-Pad29)") (class "Default")
      (node (ref "U1") (pin "29") (pinfunction "P2.3/TA2.0_29") (pintype "bidirectional"))
    )
    (net (code "51") (name "unconnected-(U1-P2.4{slash}TA2.1-Pad30)") (class "Default")
      (node (ref "U1") (pin "30") (pinfunction "P2.4/TA2.1_30") (pintype "bidirectional"))
    )
    (net (code "52") (name "unconnected-(U1-P2.5{slash}TA2.2-Pad31)") (class "Default")
      (node (ref "U1") (pin "31") (pinfunction "P2.5/TA2.2_31") (pintype "bidirectional"))
    )
    (net (code "53") (name "unconnected-(U1-P2.6{slash}RTCCLK{slash}DMAE0-Pad32)") (class "Default")
      (node (ref "U1") (pin "32") (pinfunction "P2.6/RTCCLK/DMAE0_32") (pintype "bidirectional"))
    )
    (net (code "54") (name "unconnected-(U1-P3.0{slash}UCB0SIMO{slash}UCB0SDA-Pad34)") (class "Default")
      (node (ref "U1") (pin "34") (pinfunction "P3.0/UCB0SIMO/UCB0SDA_34") (pintype "bidirectional"))
    )
    (net (code "55") (name "unconnected-(U1-P3.1{slash}UCB0SOMI{slash}UCB0SCL-Pad35)") (class "Default")
      (node (ref "U1") (pin "35") (pinfunction "P3.1/UCB0SOMI/UCB0SCL_35") (pintype "bidirectional"))
    )
    (net (code "56") (name "unconnected-(U1-P3.2{slash}UCB0CLK{slash}UCA0STE-Pad36)") (class "Default")
      (node (ref "U1") (pin "36") (pinfunction "P3.2/UCB0CLK/UCA0STE_36") (pintype "bidirectional"))
    )
    (net (code "57") (name "unconnected-(U1-P3.3{slash}UCA0TXD{slash}UCA0SIMO-Pad37)") (class "Default")
      (node (ref "U1") (pin "37") (pinfunction "P3.3/UCA0TXD/UCA0SIMO_37") (pintype "bidirectional"))
    )
    (net (code "58") (name "unconnected-(U1-P3.4{slash}UCA0RXD{slash}UCA0SOMI-Pad38)") (class "Default")
      (node (ref "U1") (pin "38") (pinfunction "P3.4/UCA0RXD/UCA0SOMI_38") (pintype "bidirectional"))
    )
    (net (code "59") (name "unconnected-(U1-P4.0{slash}PM_UCB1STE{slash}PM_UCA1CLK-Pad41)") (class "Default")
      (node (ref "U1") (pin "41") (pinfunction "P4.0/PM_UCB1STE/PM_UCA1CLK_41") (pintype "bidirectional"))
    )
    (net (code "60") (name "unconnected-(U1-P4.3{slash}PM_UCB1CLK{slash}PM_UCA1STE-Pad44)") (class "Default")
      (node (ref "U1") (pin "44") (pinfunction "P4.3/PM_UCB1CLK/PM_UCA1STE_44") (pintype "bidirectional"))
    )
    (net (code "61") (name "unconnected-(U1-P4.4{slash}PM_UCA1TXD{slash}PM_UCA1SIMO-Pad45)") (class "Default")
      (node (ref "U1") (pin "45") (pinfunction "P4.4/PM_UCA1TXD/PM_UCA1SIMO_45") (pintype "bidirectional"))
    )
    (net (code "62") (name "unconnected-(U1-P4.5{slash}PM_UCA1RXD{slash}PM_UCA1SOMI-Pad46)") (class "Default")
      (node (ref "U1") (pin "46") (pinfunction "P4.5/PM_UCA1RXD/PM_UCA1SOMI_46") (pintype "bidirectional"))
    )
    (net (code "63") (name "unconnected-(U1-P4.6{slash}PM_NONE-Pad47)") (class "Default")
      (node (ref "U1") (pin "47") (pinfunction "P4.6/PM_NONE_47") (pintype "bidirectional"))
    )
    (net (code "64") (name "unconnected-(U1-P5.0{slash}A8{slash}VREF+{slash}VEREF+-Pad9)") (class "Default")
      (node (ref "U1") (pin "9") (pinfunction "P5.0/A8/VREF+/VEREF+_9") (pintype "bidirectional"))
    )
    (net (code "65") (name "unconnected-(U1-P5.1{slash}A9{slash}VREF-{slash}VEREF--Pad10)") (class "Default")
      (node (ref "U1") (pin "10") (pinfunction "P5.1/A9/VREF-/VEREF-_10") (pintype "bidirectional"))
    )
    (net (code "66") (name "unconnected-(U1-P5.4{slash}XIN-Pad12)") (class "Default")
      (node (ref "U1") (pin "12") (pinfunction "P5.4/XIN_12") (pintype "bidirectional"))
    )
    (net (code "67") (name "unconnected-(U1-P5.5{slash}XOUT-Pad13)") (class "Default")
      (node (ref "U1") (pin "13") (pinfunction "P5.5/XOUT_13") (pintype "bidirectional"))
    )
    (net (code "68") (name "unconnected-(U1-P6.0{slash}CB0{slash}A0-Pad1)") (class "Default")
      (node (ref "U1") (pin "1") (pinfunction "P6.0/CB0/A0_1") (pintype "bidirectional"))
    )
    (net (code "69") (name "unconnected-(U1-P6.1{slash}CB1{slash}A1-Pad2)") (class "Default")
      (node (ref "U1") (pin "2") (pinfunction "P6.1/CB1/A1_2") (pintype "bidirectional"))
    )
    (net (code "70") (name "unconnected-(U1-P6.2{slash}CB2{slash}A2-Pad3)") (class "Default")
      (node (ref "U1") (pin "3") (pinfunction "P6.2/CB2/A2_3") (pintype "bidirectional"))
    )
    (net (code "71") (name "unconnected-(U1-P6.3{slash}CB3{slash}A3-Pad4)") (class "Default")
      (node (ref "U1") (pin "4") (pinfunction "P6.3/CB3/A3_4") (pintype "bidirectional"))
    )
    (net (code "72") (name "unconnected-(U1-P6.4{slash}CB4{slash}A4-Pad5)") (class "Default")
      (node (ref "U1") (pin "5") (pinfunction "P6.4/CB4/A4_5") (pintype "bidirectional"))
    )
    (net (code "73") (name "unconnected-(U1-P6.5{slash}CB5{slash}A5-Pad6)") (class "Default")
      (node (ref "U1") (pin "6") (pinfunction "P6.5/CB5/A5_6") (pintype "bidirectional"))
    )
    (net (code "74") (name "unconnected-(U1-P6.6{slash}CB6{slash}A6-Pad7)") (class "Default")
      (node (ref "U1") (pin "7") (pinfunction "P6.6/CB6/A6_7") (pintype "bidirectional"))
    )
    (net (code "75") (name "unconnected-(U1-P6.7{slash}CB7{slash}A7-Pad8)") (class "Default")
      (node (ref "U1") (pin "8") (pinfunction "P6.7/CB7/A7_8") (pintype "bidirectional"))
    )
    (net (code "76") (name "unconnected-(U2-IN1A-Pad11)") (class "Default")
      (node (ref "U2") (pin "11") (pinfunction "IN1A_11") (pintype "bidirectional"))
    )
    (net (code "77") (name "unconnected-(U2-IN1B-Pad12)") (class "Default")
      (node (ref "U2") (pin "12") (pinfunction "IN1B_12") (pintype "bidirectional"))
    )
  )
)
